# LED.net
KiCad netlist of a schematic drawn in Altium Designer
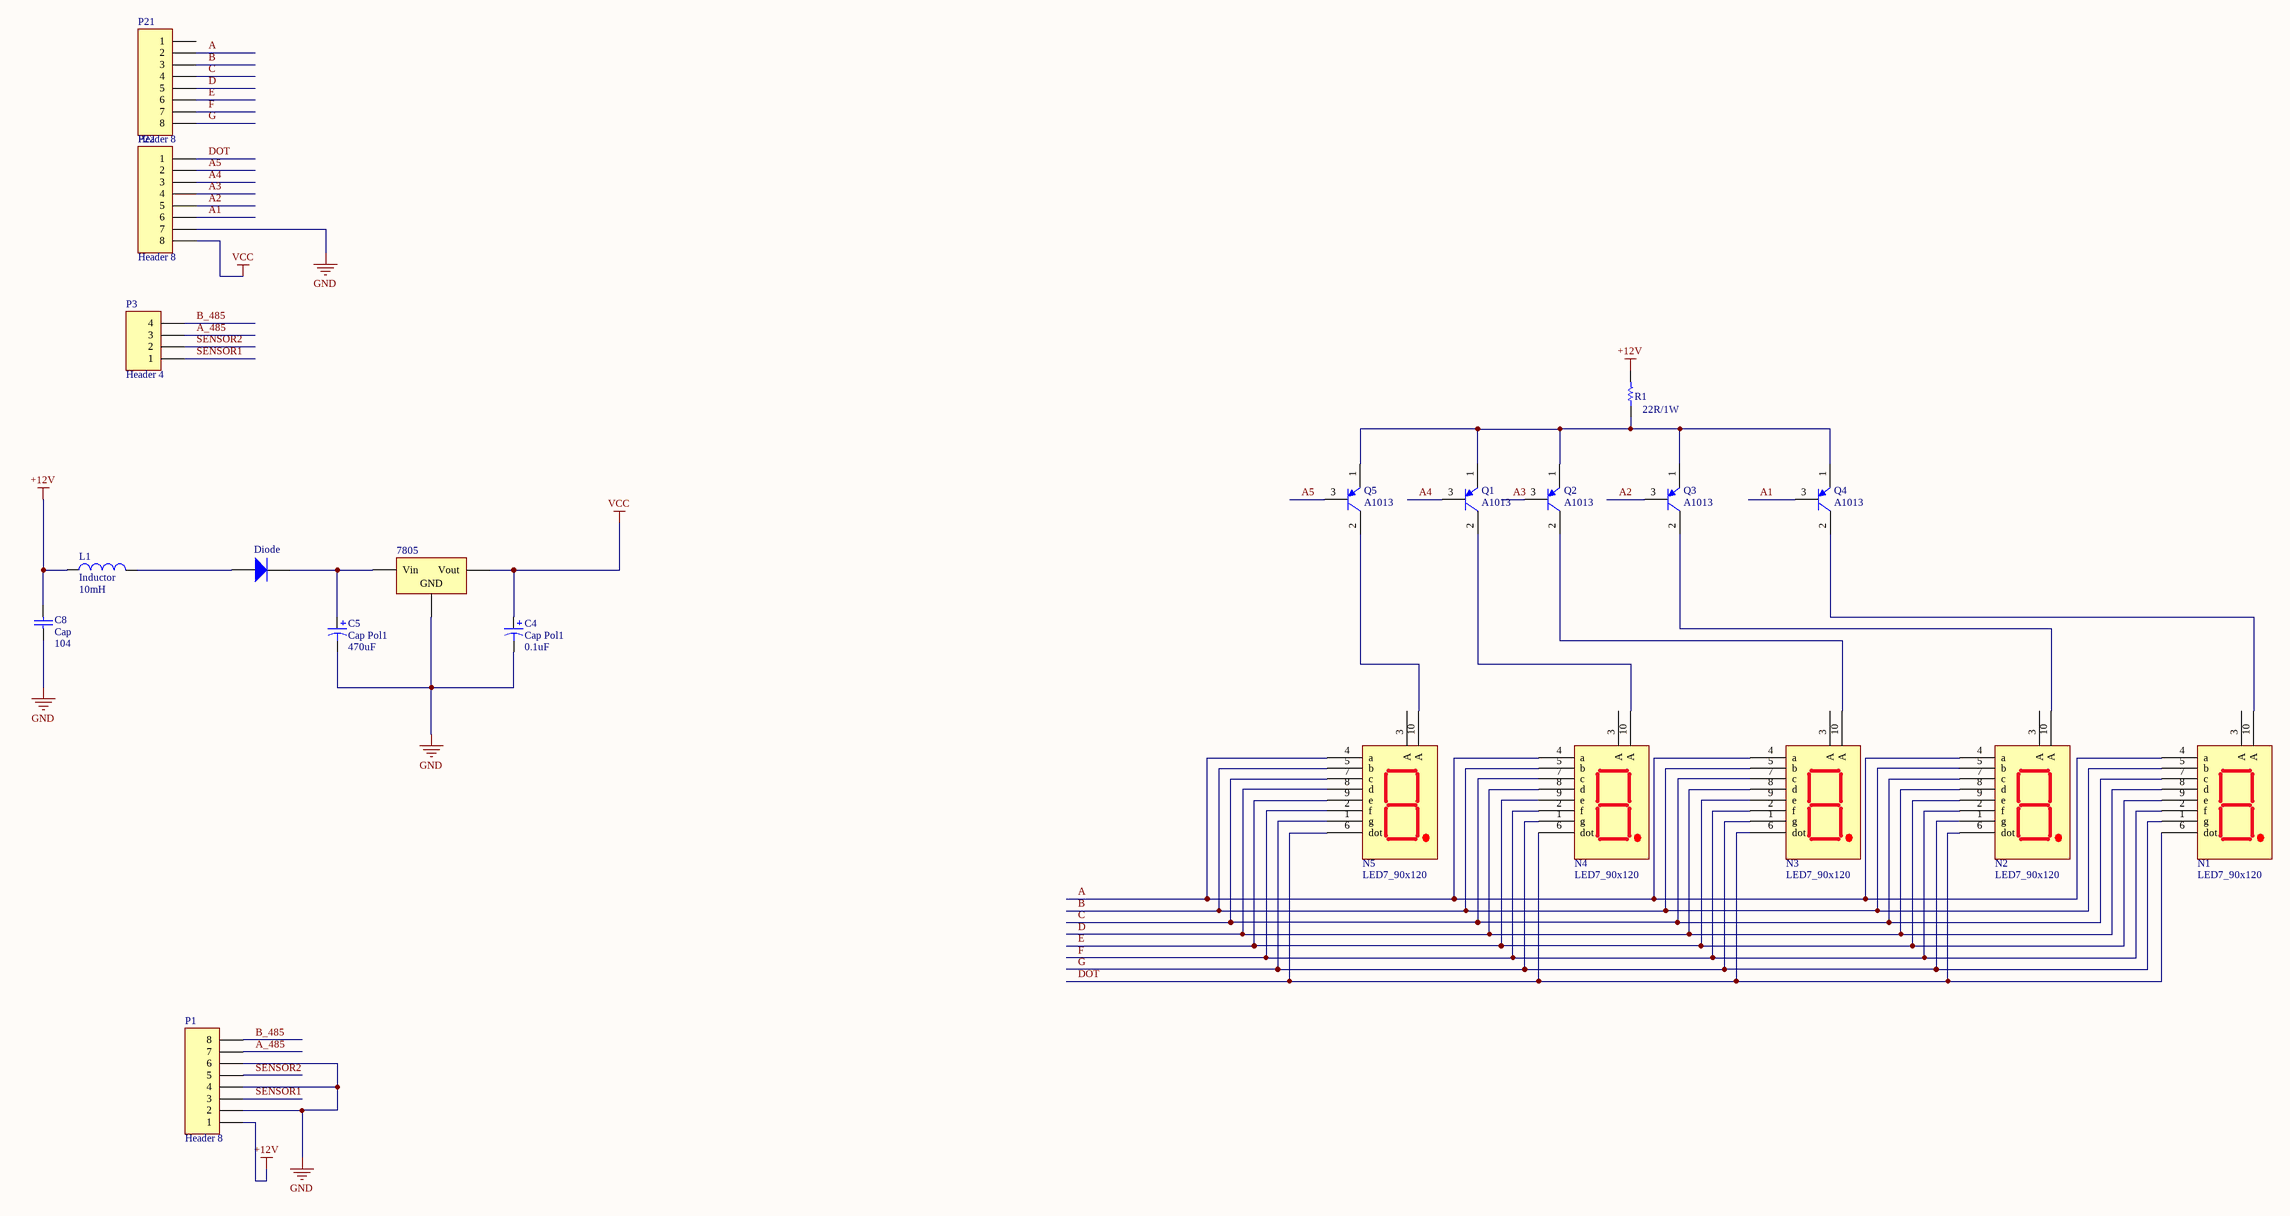
[diagram p0: LED.SchDoc]

(export (version "E")
  (design (tool "Eeschema 10.0.6"))
  (components
    (comp (ref "7805")
      (value "Volt Reg")
      (footprint "Device:78xxC")
      (description "Voltage Regulator")
      (fields (field (name "PUBLISHER") "Altium Limited"))
      (libsource (lib "Miscellaneous Devices") (part "Volt Reg"))
    )
    (comp (ref "C4")
      (value "Cap Pol1")
      (footprint "Device:tu 100uF/50v")
      (description "Polarized Capacitor (Radial)")
      (fields (field (name "ALTIUM_VALUE") "0.1uF") (field (name "PUBLISHER") "Altium Limited"))
      (libsource (lib "Miscellaneous Devices") (part "Cap Pol1"))
    )
    (comp (ref "C5")
      (value "Cap Pol1")
      (footprint "Device:TU 470uF/50V")
      (description "Polarized Capacitor (Radial)")
      (fields (field (name "ALTIUM_VALUE") "470uF") (field (name "PUBLISHER") "Altium Limited"))
      (libsource (lib "Miscellaneous Devices") (part "Cap Pol1"))
    )
    (comp (ref "C8")
      (value "Cap")
      (footprint "Device:tu_gom")
      (description "Capcitor")
      (fields (field (name "ALTIUM_VALUE") "104"))
      (libsource (lib "Device_Component") (part "Ceramic"))
    )
    (comp (ref "Diode")
      (value "Diode")
      (footprint "Device:D_2A")
      (description "Default Diode")
      (fields (field (name "PUBLISHER") "Altium Limited"))
      (libsource (lib "Miscellaneous Devices") (part "Diode"))
    )
    (comp (ref "L1")
      (value "Inductor")
      (footprint "Device:R_Nor")
      (fields (field (name "ALTIUM_VALUE") "10mH") (field (name "PUBLISHER") "Altium Limited"))
      (libsource (lib "Miscellaneous Devices") (part "Inductor"))
    )
    (comp (ref "N1")
      (value "LED7_90x120")
      (footprint "Device:LED7_90x120")
      (libsource (lib "Device_Component") (part "LED7_90x120"))
    )
    (comp (ref "N2")
      (value "LED7_90x120")
      (footprint "Device:LED7_90x120")
      (libsource (lib "Device_Component") (part "LED7_90x120"))
    )
    (comp (ref "N3")
      (value "LED7_90x120")
      (footprint "Device:LED7_90x120")
      (libsource (lib "Device_Component") (part "LED7_90x120"))
    )
    (comp (ref "N4")
      (value "LED7_90x120")
      (footprint "Device:LED7_90x120")
      (libsource (lib "Device_Component") (part "LED7_90x120"))
    )
    (comp (ref "N5")
      (value "LED7_90x120")
      (footprint "Device:LED7_90x120")
      (libsource (lib "Device_Component") (part "LED7_90x120"))
    )
    (comp (ref "P1")
      (value "Header 8")
      (footprint "Device:Coc 8")
      (description "Header, 8-Pin")
      (fields (field (name "PUBLISHER") "Altium Limited"))
      (libsource (lib "") (part "Header 8_1"))
    )
    (comp (ref "P3")
      (value "Header 4")
      (footprint "HDR1X4")
      (description "Header, 4-Pin")
      (fields (field (name "PUBLISHER") "Altium Limited"))
      (libsource (lib "Miscellaneous Connectors") (part "Header 4"))
    )
    (comp (ref "P21")
      (value "Header 8")
      (footprint "HDR1X8")
      (description "Header, 8-Pin")
      (fields (field (name "PUBLISHER") "Altium Limited"))
      (libsource (lib "Miscellaneous Connectors") (part "Header 8"))
    )
    (comp (ref "P22")
      (value "Header 8")
      (footprint "HDR1X8")
      (description "Header, 8-Pin")
      (fields (field (name "PUBLISHER") "Altium Limited"))
      (libsource (lib "Miscellaneous Connectors") (part "Header 8"))
    )
    (comp (ref "Q1")
      (value "A1013")
      (footprint "Device:A1013")
      (description "PNP Bipolar Transistor")
      (fields (field (name "PUBLISHER") "Altium Limited"))
      (libsource (lib "Miscellaneous Devices") (part "PNP"))
    )
    (comp (ref "Q2")
      (value "A1013")
      (footprint "Device:A1013")
      (description "PNP Bipolar Transistor")
      (fields (field (name "PUBLISHER") "Altium Limited"))
      (libsource (lib "Miscellaneous Devices") (part "PNP"))
    )
    (comp (ref "Q3")
      (value "A1013")
      (footprint "Device:A1013")
      (description "PNP Bipolar Transistor")
      (fields (field (name "PUBLISHER") "Altium Limited"))
      (libsource (lib "Miscellaneous Devices") (part "PNP"))
    )
    (comp (ref "Q4")
      (value "A1013")
      (footprint "Device:A1013")
      (description "PNP Bipolar Transistor")
      (fields (field (name "PUBLISHER") "Altium Limited"))
      (libsource (lib "Miscellaneous Devices") (part "PNP"))
    )
    (comp (ref "Q5")
      (value "A1013")
      (footprint "Device:A1013")
      (description "PNP Bipolar Transistor")
      (fields (field (name "PUBLISHER") "Altium Limited"))
      (libsource (lib "Miscellaneous Devices") (part "PNP"))
    )
    (comp (ref "R1")
      (value "22R/1W")
      (footprint "Device:R_CS10R/5W")
      (libsource (lib "Device_Component") (part "Res"))
    )
  )
  (nets
    (net (code "1") (name "+12V") (class "Default")
      (node (ref "C8") (pin "2") (pinfunction "2_2") (pintype "passive"))
      (node (ref "L1") (pin "1") (pinfunction "1_1") (pintype "passive"))
      (node (ref "P1") (pin "1") (pinfunction "1_1") (pintype "passive"))
      (node (ref "R1") (pin "2") (pinfunction "2_2") (pintype "passive"))
    )
    (net (code "2") (name "/A") (class "Default")
      (node (ref "N1") (pin "4") (pinfunction "a_4") (pintype "passive"))
      (node (ref "N2") (pin "4") (pinfunction "a_4") (pintype "passive"))
      (node (ref "N3") (pin "4") (pinfunction "a_4") (pintype "passive"))
      (node (ref "N4") (pin "4") (pinfunction "a_4") (pintype "passive"))
      (node (ref "N5") (pin "4") (pinfunction "a_4") (pintype "passive"))
      (node (ref "P21") (pin "2") (pinfunction "2_2") (pintype "passive"))
    )
    (net (code "3") (name "/A1") (class "Default")
      (node (ref "P22") (pin "6") (pinfunction "6_6") (pintype "passive"))
      (node (ref "Q4") (pin "3") (pinfunction "B_3") (pintype "passive"))
    )
    (net (code "4") (name "/A2") (class "Default")
      (node (ref "P22") (pin "5") (pinfunction "5_5") (pintype "passive"))
      (node (ref "Q3") (pin "3") (pinfunction "B_3") (pintype "passive"))
    )
    (net (code "5") (name "/A3") (class "Default")
      (node (ref "P22") (pin "4") (pinfunction "4_4") (pintype "passive"))
      (node (ref "Q2") (pin "3") (pinfunction "B_3") (pintype "passive"))
    )
    (net (code "6") (name "/A4") (class "Default")
      (node (ref "P22") (pin "3") (pinfunction "3_3") (pintype "passive"))
      (node (ref "Q1") (pin "3") (pinfunction "B_3") (pintype "passive"))
    )
    (net (code "7") (name "/A5") (class "Default")
      (node (ref "P22") (pin "2") (pinfunction "2_2") (pintype "passive"))
      (node (ref "Q5") (pin "3") (pinfunction "B_3") (pintype "passive"))
    )
    (net (code "8") (name "/A_485") (class "Default")
      (node (ref "P1") (pin "7") (pinfunction "7_7") (pintype "passive"))
      (node (ref "P3") (pin "3") (pinfunction "3_3") (pintype "passive"))
    )
    (net (code "9") (name "/B") (class "Default")
      (node (ref "N1") (pin "5") (pinfunction "b_5") (pintype "passive"))
      (node (ref "N2") (pin "5") (pinfunction "b_5") (pintype "passive"))
      (node (ref "N3") (pin "5") (pinfunction "b_5") (pintype "passive"))
      (node (ref "N4") (pin "5") (pinfunction "b_5") (pintype "passive"))
      (node (ref "N5") (pin "5") (pinfunction "b_5") (pintype "passive"))
      (node (ref "P21") (pin "3") (pinfunction "3_3") (pintype "passive"))
    )
    (net (code "10") (name "/B_485") (class "Default")
      (node (ref "P1") (pin "8") (pinfunction "8_8") (pintype "passive"))
      (node (ref "P3") (pin "4") (pinfunction "4_4") (pintype "passive"))
    )
    (net (code "11") (name "/C") (class "Default")
      (node (ref "N1") (pin "7") (pinfunction "c_7") (pintype "passive"))
      (node (ref "N2") (pin "7") (pinfunction "c_7") (pintype "passive"))
      (node (ref "N3") (pin "7") (pinfunction "c_7") (pintype "passive"))
      (node (ref "N4") (pin "7") (pinfunction "c_7") (pintype "passive"))
      (node (ref "N5") (pin "7") (pinfunction "c_7") (pintype "passive"))
      (node (ref "P21") (pin "4") (pinfunction "4_4") (pintype "passive"))
    )
    (net (code "12") (name "/D") (class "Default")
      (node (ref "N1") (pin "8") (pinfunction "d_8") (pintype "passive"))
      (node (ref "N2") (pin "8") (pinfunction "d_8") (pintype "passive"))
      (node (ref "N3") (pin "8") (pinfunction "d_8") (pintype "passive"))
      (node (ref "N4") (pin "8") (pinfunction "d_8") (pintype "passive"))
      (node (ref "N5") (pin "8") (pinfunction "d_8") (pintype "passive"))
      (node (ref "P21") (pin "5") (pinfunction "5_5") (pintype "passive"))
    )
    (net (code "13") (name "/DOT") (class "Default")
      (node (ref "N1") (pin "6") (pinfunction "dot_6") (pintype "passive"))
      (node (ref "N2") (pin "6") (pinfunction "dot_6") (pintype "passive"))
      (node (ref "N3") (pin "6") (pinfunction "dot_6") (pintype "passive"))
      (node (ref "N4") (pin "6") (pinfunction "dot_6") (pintype "passive"))
      (node (ref "N5") (pin "6") (pinfunction "dot_6") (pintype "passive"))
      (node (ref "P22") (pin "1") (pinfunction "1_1") (pintype "passive"))
    )
    (net (code "14") (name "/E") (class "Default")
      (node (ref "N1") (pin "9") (pinfunction "e_9") (pintype "passive"))
      (node (ref "N2") (pin "9") (pinfunction "e_9") (pintype "passive"))
      (node (ref "N3") (pin "9") (pinfunction "e_9") (pintype "passive"))
      (node (ref "N4") (pin "9") (pinfunction "e_9") (pintype "passive"))
      (node (ref "N5") (pin "9") (pinfunction "e_9") (pintype "passive"))
      (node (ref "P21") (pin "6") (pinfunction "6_6") (pintype "passive"))
    )
    (net (code "15") (name "/F") (class "Default")
      (node (ref "N1") (pin "2") (pinfunction "f_2") (pintype "passive"))
      (node (ref "N2") (pin "2") (pinfunction "f_2") (pintype "passive"))
      (node (ref "N3") (pin "2") (pinfunction "f_2") (pintype "passive"))
      (node (ref "N4") (pin "2") (pinfunction "f_2") (pintype "passive"))
      (node (ref "N5") (pin "2") (pinfunction "f_2") (pintype "passive"))
      (node (ref "P21") (pin "7") (pinfunction "7_7") (pintype "passive"))
    )
    (net (code "16") (name "/G") (class "Default")
      (node (ref "N1") (pin "1") (pinfunction "g_1") (pintype "passive"))
      (node (ref "N2") (pin "1") (pinfunction "g_1") (pintype "passive"))
      (node (ref "N3") (pin "1") (pinfunction "g_1") (pintype "passive"))
      (node (ref "N4") (pin "1") (pinfunction "g_1") (pintype "passive"))
      (node (ref "N5") (pin "1") (pinfunction "g_1") (pintype "passive"))
      (node (ref "P21") (pin "8") (pinfunction "8_8") (pintype "passive"))
    )
    (net (code "17") (name "/SENSOR1") (class "Default")
      (node (ref "P1") (pin "3") (pinfunction "3_3") (pintype "passive"))
      (node (ref "P3") (pin "1") (pinfunction "1_1") (pintype "passive"))
    )
    (net (code "18") (name "/SENSOR2") (class "Default")
      (node (ref "P1") (pin "5") (pinfunction "5_5") (pintype "passive"))
      (node (ref "P3") (pin "2") (pinfunction "2_2") (pintype "passive"))
    )
    (net (code "19") (name "GND") (class "Default")
      (node (ref "7805") (pin "2") (pinfunction "GND_2") (pintype "passive"))
      (node (ref "C4") (pin "2") (pinfunction "2_2") (pintype "passive"))
      (node (ref "C5") (pin "2") (pinfunction "2_2") (pintype "passive"))
      (node (ref "C8") (pin "1") (pinfunction "1_1") (pintype "passive"))
      (node (ref "P1") (pin "2") (pinfunction "2_2") (pintype "passive"))
      (node (ref "P1") (pin "4") (pinfunction "4_4") (pintype "passive"))
      (node (ref "P1") (pin "6") (pinfunction "6_6") (pintype "passive"))
      (node (ref "P22") (pin "7") (pinfunction "7_7") (pintype "passive"))
    )
    (net (code "20") (name "Net-(7805-Vin)") (class "Default")
      (node (ref "7805") (pin "1") (pinfunction "Vin_1") (pintype "passive"))
      (node (ref "C5") (pin "1") (pinfunction "1_1") (pintype "passive"))
      (node (ref "Diode") (pin "2") (pinfunction "K_2") (pintype "passive"))
    )
    (net (code "21") (name "Net-(Diode-A)") (class "Default")
      (node (ref "Diode") (pin "1") (pinfunction "A_1") (pintype "passive"))
      (node (ref "L1") (pin "2") (pinfunction "2_2") (pintype "passive"))
    )
    (net (code "22") (name "Net-(Q1-C)") (class "Default")
      (node (ref "N4") (pin "10") (pinfunction "A_10") (pintype "passive"))
      (node (ref "Q1") (pin "2") (pinfunction "C_2") (pintype "passive"))
    )
    (net (code "23") (name "Net-(Q1-E)") (class "Default")
      (node (ref "Q1") (pin "1") (pinfunction "E_1") (pintype "passive"))
      (node (ref "Q2") (pin "1") (pinfunction "E_1") (pintype "passive"))
      (node (ref "Q3") (pin "1") (pinfunction "E_1") (pintype "passive"))
      (node (ref "Q4") (pin "1") (pinfunction "E_1") (pintype "passive"))
      (node (ref "Q5") (pin "1") (pinfunction "E_1") (pintype "passive"))
      (node (ref "R1") (pin "1") (pinfunction "1_1") (pintype "passive"))
    )
    (net (code "24") (name "Net-(Q2-C)") (class "Default")
      (node (ref "N3") (pin "10") (pinfunction "A_10") (pintype "passive"))
      (node (ref "Q2") (pin "2") (pinfunction "C_2") (pintype "passive"))
    )
    (net (code "25") (name "Net-(Q3-C)") (class "Default")
      (node (ref "N2") (pin "10") (pinfunction "A_10") (pintype "passive"))
      (node (ref "Q3") (pin "2") (pinfunction "C_2") (pintype "passive"))
    )
    (net (code "26") (name "Net-(Q4-C)") (class "Default")
      (node (ref "N1") (pin "10") (pinfunction "A_10") (pintype "passive"))
      (node (ref "Q4") (pin "2") (pinfunction "C_2") (pintype "passive"))
    )
    (net (code "27") (name "Net-(Q5-C)") (class "Default")
      (node (ref "N5") (pin "10") (pinfunction "A_10") (pintype "passive"))
      (node (ref "Q5") (pin "2") (pinfunction "C_2") (pintype "passive"))
    )
    (net (code "28") (name "VCC") (class "Default")
      (node (ref "7805") (pin "3") (pinfunction "Vout_3") (pintype "passive"))
      (node (ref "C4") (pin "1") (pinfunction "1_1") (pintype "passive"))
      (node (ref "P22") (pin "8") (pinfunction "8_8") (pintype "passive"))
    )
    (net (code "29") (name "unconnected-(N1-A-Pad3)") (class "Default")
      (node (ref "N1") (pin "3") (pinfunction "A_3") (pintype "passive"))
    )
    (net (code "30") (name "unconnected-(N2-A-Pad3)") (class "Default")
      (node (ref "N2") (pin "3") (pinfunction "A_3") (pintype "passive"))
    )
    (net (code "31") (name "unconnected-(N3-A-Pad3)") (class "Default")
      (node (ref "N3") (pin "3") (pinfunction "A_3") (pintype "passive"))
    )
    (net (code "32") (name "unconnected-(N4-A-Pad3)") (class "Default")
      (node (ref "N4") (pin "3") (pinfunction "A_3") (pintype "passive"))
    )
    (net (code "33") (name "unconnected-(N5-A-Pad3)") (class "Default")
      (node (ref "N5") (pin "3") (pinfunction "A_3") (pintype "passive"))
    )
    (net (code "34") (name "unconnected-(P21-Pad1)") (class "Default")
      (node (ref "P21") (pin "1") (pinfunction "1_1") (pintype "passive"))
    )
  )
)
